# Adafruit_Ultimate_GPS_Hat.net
KiCad netlist of a schematic drawn in EAGLE
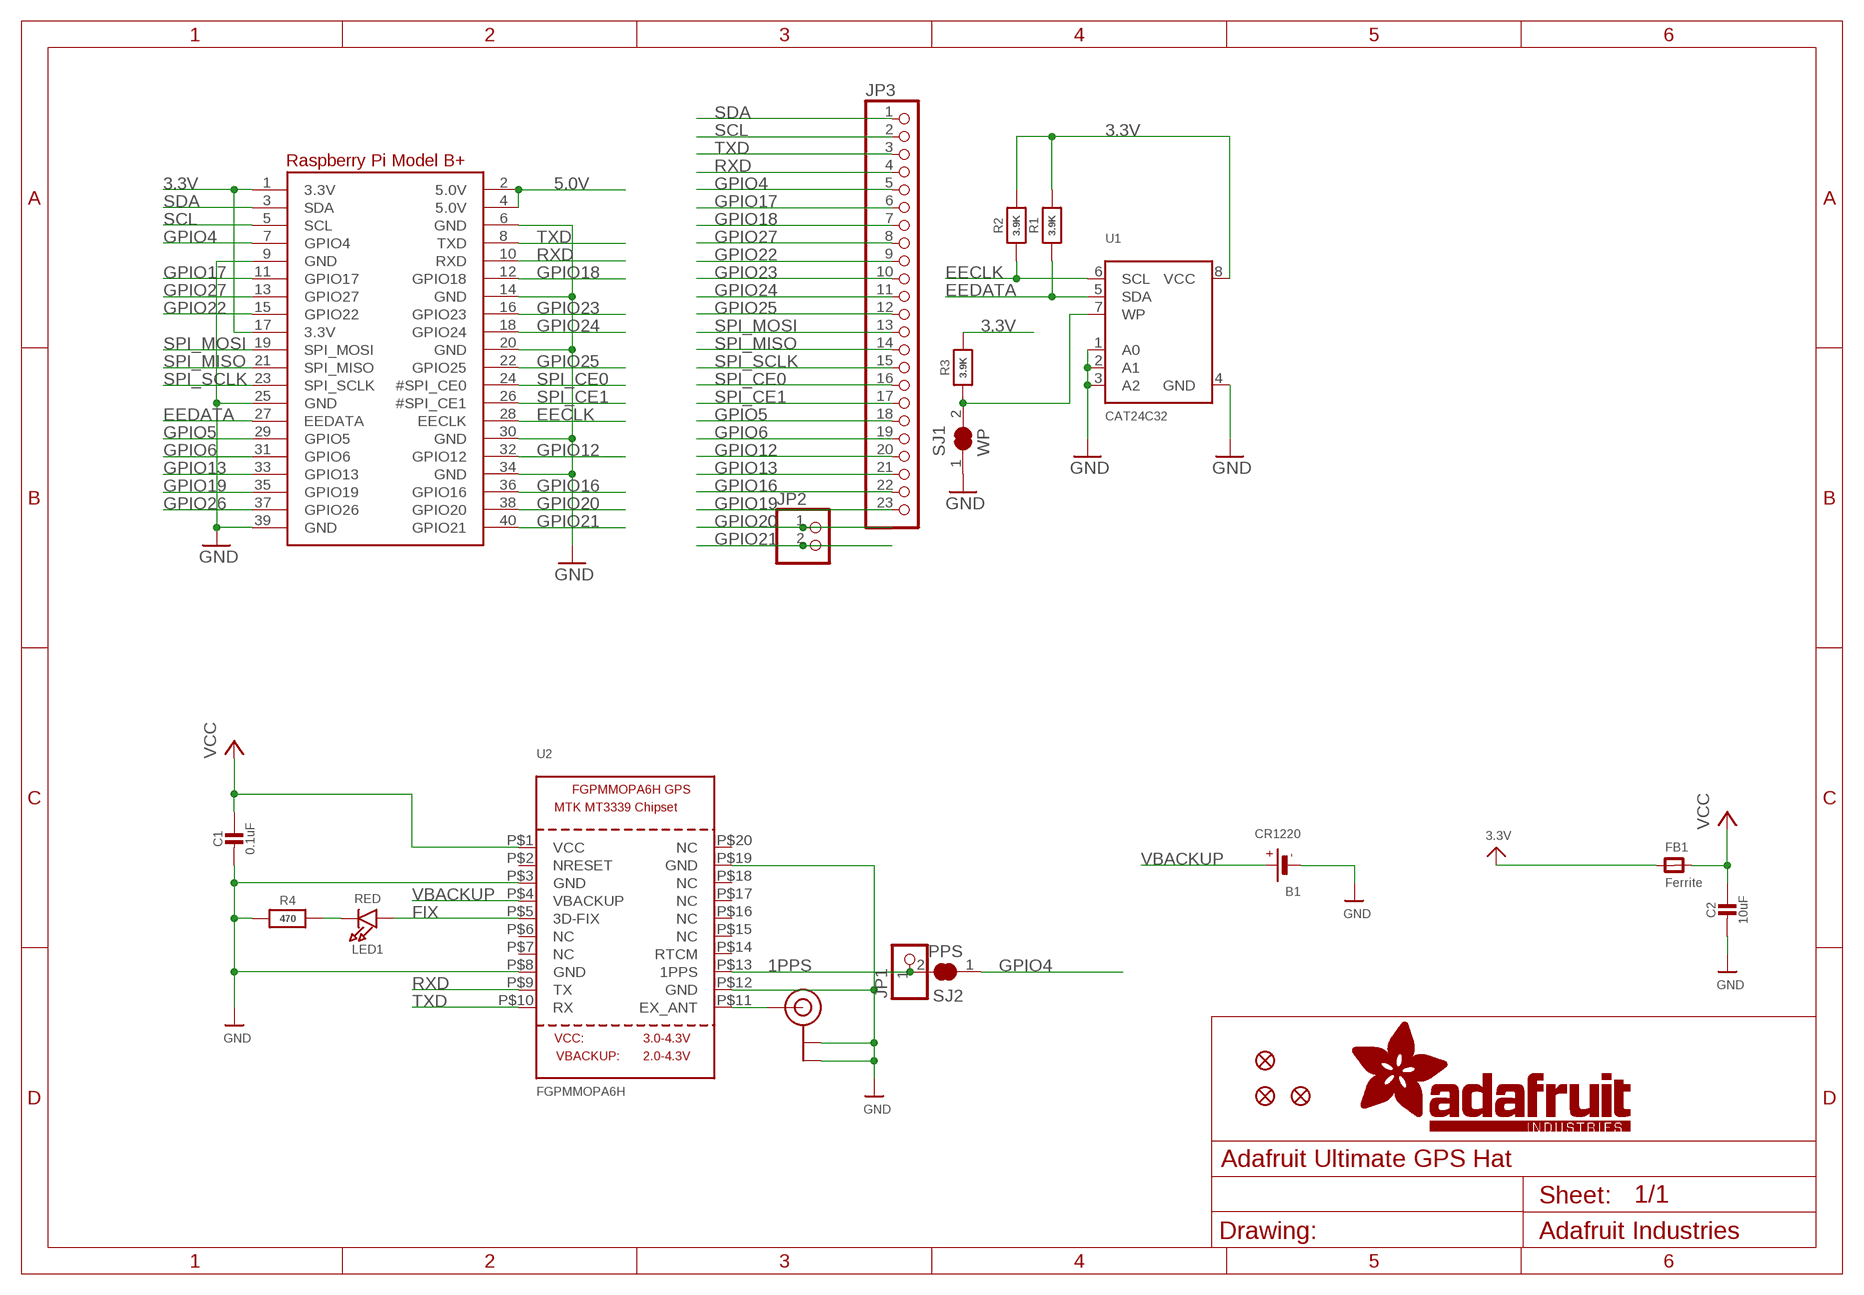
[diagram p0: schematic, sheet 1]

(export (version "E")
  (design (tool "Eeschema 10.0.6"))
  (components
    (comp (ref "B1")
      (value "CR1220")
      (footprint "eagle-import:CR1220")
      (libsource (lib "eagle-import") (part "BATTERYCR1220_SMT"))
    )
    (comp (ref "C1")
      (value "0.1uF")
      (footprint "eagle-import:0805-NO")
      (libsource (lib "eagle-import") (part "CAP_CERAMIC0805-NOOUTLINE"))
    )
    (comp (ref "C2")
      (value "10uF")
      (footprint "eagle-import:0805-NO")
      (libsource (lib "eagle-import") (part "CAP_CERAMIC0805-NOOUTLINE"))
    )
    (comp (ref "FB1")
      (value "Ferrite")
      (footprint "eagle-import:0805")
      (libsource (lib "eagle-import") (part "FERRITE0805"))
    )
    (comp (ref "FID1")
      (value "FIDUCIAL_1MM")
      (footprint "eagle-import:FIDUCIAL_1MM")
      (libsource (lib "eagle-import") (part "FIDUCIAL_1MM"))
    )
    (comp (ref "FID2")
      (value "FIDUCIAL_1MM")
      (footprint "eagle-import:FIDUCIAL_1MM")
      (libsource (lib "eagle-import") (part "FIDUCIAL_1MM"))
    )
    (comp (ref "FID3")
      (value "FIDUCIAL_1MM")
      (footprint "eagle-import:FIDUCIAL_1MM")
      (libsource (lib "eagle-import") (part "FIDUCIAL_1MM"))
    )
    (comp (ref "JP1")
      (value "PINHD-1X1CB")
      (footprint "eagle-import:1X01-CLEANBIG")
      (libsource (lib "eagle-import") (part "PINHD-1X1CB"))
    )
    (comp (ref "JP2")
      (value "HEADER-1X2ROUND")
      (footprint "eagle-import:1X02_ROUND")
      (libsource (lib "eagle-import") (part "HEADER-1X2ROUND"))
    )
    (comp (ref "JP3")
      (value "HEADER-1X23")
      (footprint "eagle-import:1X23_ROUND_70MIL")
      (libsource (lib "eagle-import") (part "HEADER-1X23"))
    )
    (comp (ref "LED1")
      (value "RED")
      (footprint "eagle-import:CHIPLED_0805")
      (libsource (lib "eagle-import") (part "LED0805"))
    )
    (comp (ref "R1")
      (value "3.9K")
      (footprint "eagle-import:0805-NO")
      (libsource (lib "eagle-import") (part "RESISTOR0805_NOOUTLINE"))
    )
    (comp (ref "R2")
      (value "3.9K")
      (footprint "eagle-import:0805-NO")
      (libsource (lib "eagle-import") (part "RESISTOR0805_NOOUTLINE"))
    )
    (comp (ref "R3")
      (value "3.9K")
      (footprint "eagle-import:0805-NO")
      (libsource (lib "eagle-import") (part "RESISTOR0805_NOOUTLINE"))
    )
    (comp (ref "R4")
      (value "470")
      (footprint "eagle-import:0805-NO")
      (libsource (lib "eagle-import") (part "RESISTOR0805_NOOUTLINE"))
    )
    (comp (ref "RPI1")
      (value "RASPBERRYPI_BPLUS_HATSLOTS")
      (footprint "eagle-import:PI_HAT_SLOTS")
      (libsource (lib "eagle-import") (part "RASPBERRYPI_BPLUS_HATSLOTS"))
    )
    (comp (ref "SJ1")
      (value "WP")
      (footprint "eagle-import:SOLDERJUMPER_CLOSEDWIRE")
      (libsource (lib "eagle-import") (part "SOLDERJUMPER_CLOSED"))
    )
    (comp (ref "SJ2")
      (value "PPS")
      (footprint "eagle-import:SOLDERJUMPER_CLOSEDWIRE")
      (libsource (lib "eagle-import") (part "SOLDERJUMPER_CLOSED"))
    )
    (comp (ref "U$20")
      (value "U.FL")
      (footprint "eagle-import:U.FL")
      (libsource (lib "eagle-import") (part "U.FL"))
    )
    (comp (ref "U1")
      (value "CAT24C32")
      (footprint "eagle-import:SOIC8_150MIL")
      (libsource (lib "eagle-import") (part "EEPROM_I2C_SOIC8_GENERIC"))
    )
    (comp (ref "U2")
      (value "FGPMMOPA6H")
      (footprint "eagle-import:FGPMMOPA6H")
      (libsource (lib "eagle-import") (part "GPS_FGPMMOPA6H"))
    )
  )
  (nets
    (net (code "1") (name "/1PPS") (class "Default")
      (node (ref "JP1") (pin "1") (pinfunction "1_1") (pintype "passive"))
      (node (ref "SJ2") (pin "2") (pinfunction "2_2") (pintype "passive"))
      (node (ref "U2") (pin "P$13") (pinfunction "1PPS_P$13") (pintype "bidirectional"))
    )
    (net (code "2") (name "/5.0V") (class "Default")
      (node (ref "RPI1") (pin "2") (pinfunction "5.0V_2") (pintype "power_in"))
      (node (ref "RPI1") (pin "4") (pinfunction "5.0V_4") (pintype "power_in"))
    )
    (net (code "3") (name "/EECLK") (class "Default")
      (node (ref "R2") (pin "1") (pinfunction "1_1") (pintype "passive"))
      (node (ref "RPI1") (pin "28") (pinfunction "EECLK_28") (pintype "bidirectional"))
      (node (ref "U1") (pin "6") (pinfunction "SCL_6") (pintype "input"))
    )
    (net (code "4") (name "/EEDATA") (class "Default")
      (node (ref "R1") (pin "1") (pinfunction "1_1") (pintype "passive"))
      (node (ref "RPI1") (pin "27") (pinfunction "EEDATA_27") (pintype "bidirectional"))
      (node (ref "U1") (pin "5") (pinfunction "SDA_5") (pintype "bidirectional"))
    )
    (net (code "5") (name "/FIX") (class "Default")
      (node (ref "LED1") (pin "A") (pinfunction "A_A") (pintype "passive"))
      (node (ref "U2") (pin "P$5") (pinfunction "3D-FIX_P$5") (pintype "bidirectional"))
    )
    (net (code "6") (name "/GPIO4") (class "Default")
      (node (ref "JP3") (pin "5") (pinfunction "5_5") (pintype "passive"))
      (node (ref "RPI1") (pin "7") (pinfunction "GPIO4_7") (pintype "bidirectional"))
      (node (ref "SJ2") (pin "1") (pinfunction "1_1") (pintype "passive"))
    )
    (net (code "7") (name "/GPIO5") (class "Default")
      (node (ref "JP3") (pin "18") (pinfunction "18_18") (pintype "passive"))
      (node (ref "RPI1") (pin "29") (pinfunction "GPIO5_29") (pintype "bidirectional"))
    )
    (net (code "8") (name "/GPIO6") (class "Default")
      (node (ref "JP3") (pin "19") (pinfunction "19_19") (pintype "passive"))
      (node (ref "RPI1") (pin "31") (pinfunction "GPIO6_31") (pintype "bidirectional"))
    )
    (net (code "9") (name "/GPIO12") (class "Default")
      (node (ref "JP3") (pin "20") (pinfunction "20_20") (pintype "passive"))
      (node (ref "RPI1") (pin "32") (pinfunction "GPIO12_32") (pintype "bidirectional"))
    )
    (net (code "10") (name "/GPIO13") (class "Default")
      (node (ref "JP3") (pin "21") (pinfunction "21_21") (pintype "passive"))
      (node (ref "RPI1") (pin "33") (pinfunction "GPIO13_33") (pintype "bidirectional"))
    )
    (net (code "11") (name "/GPIO16") (class "Default")
      (node (ref "JP3") (pin "22") (pinfunction "22_22") (pintype "passive"))
      (node (ref "RPI1") (pin "36") (pinfunction "GPIO16_36") (pintype "bidirectional"))
    )
    (net (code "12") (name "/GPIO17") (class "Default")
      (node (ref "JP3") (pin "6") (pinfunction "6_6") (pintype "passive"))
      (node (ref "RPI1") (pin "11") (pinfunction "GPIO17_11") (pintype "bidirectional"))
    )
    (net (code "13") (name "/GPIO18") (class "Default")
      (node (ref "JP3") (pin "7") (pinfunction "7_7") (pintype "passive"))
      (node (ref "RPI1") (pin "12") (pinfunction "GPIO18_12") (pintype "bidirectional"))
    )
    (net (code "14") (name "/GPIO19") (class "Default")
      (node (ref "JP3") (pin "23") (pinfunction "23_23") (pintype "passive"))
      (node (ref "RPI1") (pin "35") (pinfunction "GPIO19_35") (pintype "bidirectional"))
    )
    (net (code "15") (name "/GPIO20") (class "Default")
      (node (ref "JP2") (pin "1") (pinfunction "1_1") (pintype "passive"))
      (node (ref "RPI1") (pin "38") (pinfunction "GPIO20_38") (pintype "bidirectional"))
    )
    (net (code "16") (name "/GPIO21") (class "Default")
      (node (ref "JP2") (pin "2") (pinfunction "2_2") (pintype "passive"))
      (node (ref "RPI1") (pin "40") (pinfunction "GPIO21_40") (pintype "bidirectional"))
    )
    (net (code "17") (name "/GPIO22") (class "Default")
      (node (ref "JP3") (pin "9") (pinfunction "9_9") (pintype "passive"))
      (node (ref "RPI1") (pin "15") (pinfunction "GPIO22_15") (pintype "bidirectional"))
    )
    (net (code "18") (name "/GPIO23") (class "Default")
      (node (ref "JP3") (pin "10") (pinfunction "10_10") (pintype "passive"))
      (node (ref "RPI1") (pin "16") (pinfunction "GPIO23_16") (pintype "bidirectional"))
    )
    (net (code "19") (name "/GPIO24") (class "Default")
      (node (ref "JP3") (pin "11") (pinfunction "11_11") (pintype "passive"))
      (node (ref "RPI1") (pin "18") (pinfunction "GPIO24_18") (pintype "bidirectional"))
    )
    (net (code "20") (name "/GPIO25") (class "Default")
      (node (ref "JP3") (pin "12") (pinfunction "12_12") (pintype "passive"))
      (node (ref "RPI1") (pin "22") (pinfunction "GPIO25_22") (pintype "bidirectional"))
    )
    (net (code "21") (name "/GPIO26") (class "Default")
      (node (ref "RPI1") (pin "37") (pinfunction "GPIO26_37") (pintype "bidirectional"))
    )
    (net (code "22") (name "/GPIO27") (class "Default")
      (node (ref "JP3") (pin "8") (pinfunction "8_8") (pintype "passive"))
      (node (ref "RPI1") (pin "13") (pinfunction "GPIO27_13") (pintype "bidirectional"))
    )
    (net (code "23") (name "/RXD") (class "Default")
      (node (ref "JP3") (pin "4") (pinfunction "4_4") (pintype "passive"))
      (node (ref "RPI1") (pin "10") (pinfunction "RXD_10") (pintype "bidirectional"))
      (node (ref "U2") (pin "P$9") (pinfunction "TX_P$9") (pintype "bidirectional"))
    )
    (net (code "24") (name "/SCL") (class "Default")
      (node (ref "JP3") (pin "2") (pinfunction "2_2") (pintype "passive"))
      (node (ref "RPI1") (pin "5") (pinfunction "SCL_5") (pintype "bidirectional"))
    )
    (net (code "25") (name "/SDA") (class "Default")
      (node (ref "JP3") (pin "1") (pinfunction "1_1") (pintype "passive"))
      (node (ref "RPI1") (pin "3") (pinfunction "SDA_3") (pintype "bidirectional"))
    )
    (net (code "26") (name "/SPI_CE0") (class "Default")
      (node (ref "JP3") (pin "16") (pinfunction "16_16") (pintype "passive"))
      (node (ref "RPI1") (pin "24") (pinfunction "#SPI_CE0_24") (pintype "bidirectional"))
    )
    (net (code "27") (name "/SPI_CE1") (class "Default")
      (node (ref "JP3") (pin "17") (pinfunction "17_17") (pintype "passive"))
      (node (ref "RPI1") (pin "26") (pinfunction "#SPI_CE1_26") (pintype "bidirectional"))
    )
    (net (code "28") (name "/SPI_MISO") (class "Default")
      (node (ref "JP3") (pin "14") (pinfunction "14_14") (pintype "passive"))
      (node (ref "RPI1") (pin "21") (pinfunction "SPI_MISO_21") (pintype "bidirectional"))
    )
    (net (code "29") (name "/SPI_MOSI") (class "Default")
      (node (ref "JP3") (pin "13") (pinfunction "13_13") (pintype "passive"))
      (node (ref "RPI1") (pin "19") (pinfunction "SPI_MOSI_19") (pintype "bidirectional"))
    )
    (net (code "30") (name "/SPI_SCLK") (class "Default")
      (node (ref "JP3") (pin "15") (pinfunction "15_15") (pintype "passive"))
      (node (ref "RPI1") (pin "23") (pinfunction "SPI_SCLK_23") (pintype "bidirectional"))
    )
    (net (code "31") (name "/TXD") (class "Default")
      (node (ref "JP3") (pin "3") (pinfunction "3_3") (pintype "passive"))
      (node (ref "RPI1") (pin "8") (pinfunction "TXD_8") (pintype "bidirectional"))
      (node (ref "U2") (pin "P$10") (pinfunction "RX_P$10") (pintype "bidirectional"))
    )
    (net (code "32") (name "/VBACKUP") (class "Default")
      (node (ref "B1") (pin "+$1") (pinfunction "+_+$1") (pintype "passive"))
      (node (ref "B1") (pin "+$2") (pinfunction "+_+$2") (pintype "passive"))
      (node (ref "U2") (pin "P$4") (pinfunction "VBACKUP_P$4") (pintype "bidirectional"))
    )
    (net (code "33") (name "3.3V") (class "Default")
      (node (ref "FB1") (pin "1") (pinfunction "P$1_1") (pintype "passive"))
      (node (ref "R1") (pin "2") (pinfunction "2_2") (pintype "passive"))
      (node (ref "R2") (pin "2") (pinfunction "2_2") (pintype "passive"))
      (node (ref "R3") (pin "2") (pinfunction "2_2") (pintype "passive"))
      (node (ref "RPI1") (pin "1") (pinfunction "3.3V_1") (pintype "power_in"))
      (node (ref "RPI1") (pin "17") (pinfunction "3.3V_17") (pintype "power_in"))
      (node (ref "U1") (pin "8") (pinfunction "VCC_8") (pintype "power_in"))
    )
    (net (code "34") (name "GND") (class "Default")
      (node (ref "B1") (pin "-") (pinfunction "-_-") (pintype "passive"))
      (node (ref "C1") (pin "2") (pinfunction "2_2") (pintype "passive"))
      (node (ref "C2") (pin "2") (pinfunction "2_2") (pintype "passive"))
      (node (ref "R4") (pin "1") (pinfunction "1_1") (pintype "passive"))
      (node (ref "RPI1") (pin "14") (pinfunction "GND_14") (pintype "power_in"))
      (node (ref "RPI1") (pin "20") (pinfunction "GND_20") (pintype "power_in"))
      (node (ref "RPI1") (pin "25") (pinfunction "GND_25") (pintype "power_in"))
      (node (ref "RPI1") (pin "30") (pinfunction "GND_30") (pintype "power_in"))
      (node (ref "RPI1") (pin "34") (pinfunction "GND_34") (pintype "power_in"))
      (node (ref "RPI1") (pin "39") (pinfunction "GND_39") (pintype "power_in"))
      (node (ref "RPI1") (pin "6") (pinfunction "GND_6") (pintype "power_in"))
      (node (ref "RPI1") (pin "9") (pinfunction "GND_9") (pintype "power_in"))
      (node (ref "SJ1") (pin "1") (pinfunction "1_1") (pintype "passive"))
      (node (ref "U$20") (pin "P$1") (pinfunction "GND_P$1") (pintype "bidirectional"))
      (node (ref "U$20") (pin "P$2") (pinfunction "GND_P$2") (pintype "bidirectional"))
      (node (ref "U1") (pin "1") (pinfunction "A0_1") (pintype "input"))
      (node (ref "U1") (pin "2") (pinfunction "A1_2") (pintype "input"))
      (node (ref "U1") (pin "3") (pinfunction "A2_3") (pintype "input"))
      (node (ref "U1") (pin "4") (pinfunction "GND_4") (pintype "power_in"))
      (node (ref "U2") (pin "P$12") (pinfunction "GND_P$12") (pintype "bidirectional"))
      (node (ref "U2") (pin "P$19") (pinfunction "GND_P$19") (pintype "bidirectional"))
      (node (ref "U2") (pin "P$3") (pinfunction "GND_P$3") (pintype "bidirectional"))
      (node (ref "U2") (pin "P$8") (pinfunction "GND_P$8") (pintype "bidirectional"))
    )
    (net (code "35") (name "Net-(LED1-PadC)") (class "Default")
      (node (ref "LED1") (pin "C") (pinfunction "C_C") (pintype "passive"))
      (node (ref "R4") (pin "2") (pinfunction "2_2") (pintype "passive"))
    )
    (net (code "36") (name "Net-(U$20-SIGNAL)") (class "Default")
      (node (ref "U$20") (pin "P$3") (pinfunction "SIGNAL_P$3") (pintype "bidirectional"))
      (node (ref "U2") (pin "P$11") (pinfunction "EX_ANT_P$11") (pintype "bidirectional"))
    )
    (net (code "37") (name "Net-(U1-WP)") (class "Default")
      (node (ref "R3") (pin "1") (pinfunction "1_1") (pintype "passive"))
      (node (ref "SJ1") (pin "2") (pinfunction "2_2") (pintype "passive"))
      (node (ref "U1") (pin "7") (pinfunction "WP_7") (pintype "input"))
    )
    (net (code "38") (name "VCC") (class "Default")
      (node (ref "C1") (pin "1") (pinfunction "1_1") (pintype "passive"))
      (node (ref "C2") (pin "1") (pinfunction "1_1") (pintype "passive"))
      (node (ref "FB1") (pin "2") (pinfunction "P$2_2") (pintype "passive"))
      (node (ref "U2") (pin "P$1") (pinfunction "VCC_P$1") (pintype "bidirectional"))
    )
    (net (code "39") (name "unconnected-(U2-NC-PadP$6)") (class "Default")
      (node (ref "U2") (pin "P$6") (pinfunction "NC_P$6") (pintype "bidirectional"))
    )
    (net (code "40") (name "unconnected-(U2-NC-PadP$7)") (class "Default")
      (node (ref "U2") (pin "P$7") (pinfunction "NC_P$7") (pintype "bidirectional"))
    )
    (net (code "41") (name "unconnected-(U2-NC-PadP$15)") (class "Default")
      (node (ref "U2") (pin "P$15") (pinfunction "NC_P$15") (pintype "bidirectional"))
    )
    (net (code "42") (name "unconnected-(U2-NC-PadP$16)") (class "Default")
      (node (ref "U2") (pin "P$16") (pinfunction "NC_P$16") (pintype "bidirectional"))
    )
    (net (code "43") (name "unconnected-(U2-NC-PadP$17)") (class "Default")
      (node (ref "U2") (pin "P$17") (pinfunction "NC_P$17") (pintype "bidirectional"))
    )
    (net (code "44") (name "unconnected-(U2-NC-PadP$18)") (class "Default")
      (node (ref "U2") (pin "P$18") (pinfunction "NC_P$18") (pintype "bidirectional"))
    )
    (net (code "45") (name "unconnected-(U2-NC-PadP$20)") (class "Default")
      (node (ref "U2") (pin "P$20") (pinfunction "NC_P$20") (pintype "bidirectional"))
    )
    (net (code "46") (name "unconnected-(U2-NRESET-PadP$2)") (class "Default")
      (node (ref "U2") (pin "P$2") (pinfunction "NRESET_P$2") (pintype "bidirectional"))
    )
    (net (code "47") (name "unconnected-(U2-RTCM-PadP$14)") (class "Default")
      (node (ref "U2") (pin "P$14") (pinfunction "RTCM_P$14") (pintype "bidirectional"))
    )
  )
)
